# project.net
KiCad netlist of a schematic drawn in EAGLE
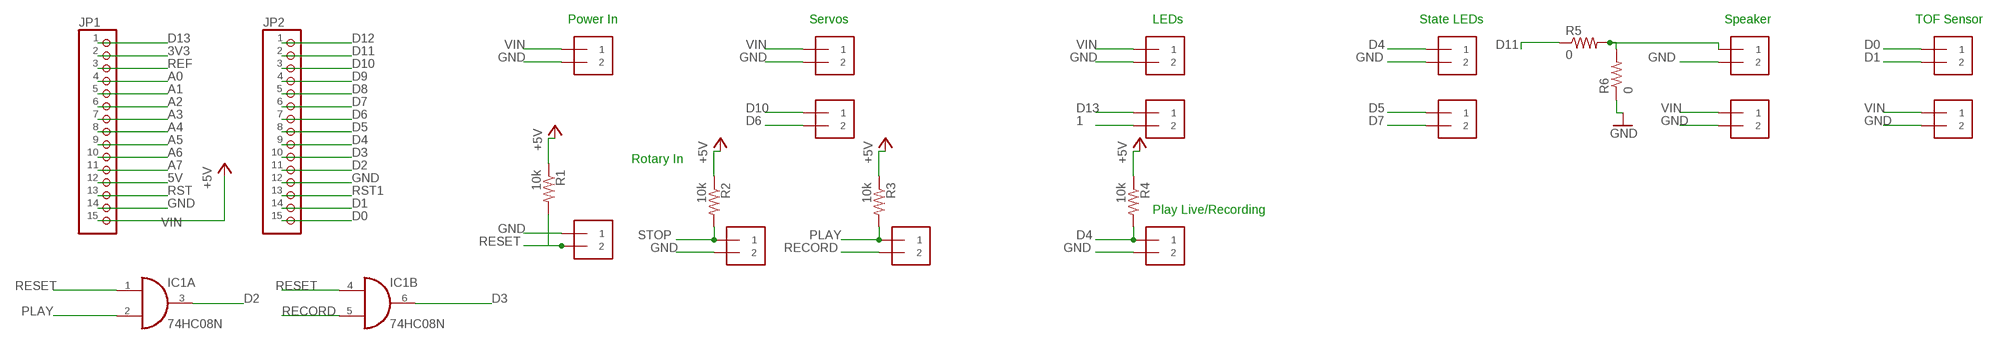
[diagram p0: schematic, sheet 1]

(export (version "E")
  (design (tool "Eeschema 10.0.6"))
  (components
    (comp (ref "IC1")
      (value "74HC08N")
      (footprint "eagle-import:DIL14")
      (libsource (lib "eagle-import") (part "7408NHC"))
    )
    (comp (ref "J1")
      (value "1X2-3.5MM")
      (footprint "eagle-import:1X2-3.5MM")
      (libsource (lib "eagle-import") (part "1X2-3.5MM"))
    )
    (comp (ref "J2")
      (value "1X2-3.5MM")
      (footprint "eagle-import:1X2-3.5MM")
      (libsource (lib "eagle-import") (part "1X2-3.5MM"))
    )
    (comp (ref "J3")
      (value "1X2-3.5MM")
      (footprint "eagle-import:1X2-3.5MM")
      (libsource (lib "eagle-import") (part "1X2-3.5MM"))
    )
    (comp (ref "J4")
      (value "1X2-3.5MM")
      (footprint "eagle-import:1X2-3.5MM")
      (libsource (lib "eagle-import") (part "1X2-3.5MM"))
    )
    (comp (ref "JP1")
      (value "PINHD-1X15")
      (footprint "eagle-import:1X15")
      (libsource (lib "eagle-import") (part "PINHD-1X15"))
    )
    (comp (ref "JP2")
      (value "PINHD-1X15")
      (footprint "eagle-import:1X15")
      (libsource (lib "eagle-import") (part "PINHD-1X15"))
    )
    (comp (ref "LED1")
      (value "1X2-3.5MM")
      (footprint "eagle-import:1X2-3.5MM")
      (libsource (lib "eagle-import") (part "1X2-3.5MM"))
    )
    (comp (ref "LED2_3")
      (value "1X2-3.5MM")
      (footprint "eagle-import:1X2-3.5MM")
      (libsource (lib "eagle-import") (part "1X2-3.5MM"))
    )
    (comp (ref "LED_PWR")
      (value "1X2-3.5MM")
      (footprint "eagle-import:1X2-3.5MM")
      (libsource (lib "eagle-import") (part "1X2-3.5MM"))
    )
    (comp (ref "LED_SIG")
      (value "1X2-3.5MM")
      (footprint "eagle-import:1X2-3.5MM")
      (libsource (lib "eagle-import") (part "1X2-3.5MM"))
    )
    (comp (ref "POWER")
      (value "1X2-3.5MM")
      (footprint "eagle-import:1X2-3.5MM")
      (libsource (lib "eagle-import") (part "1X2-3.5MM"))
    )
    (comp (ref "R1")
      (value "10k")
      (footprint "eagle-import:M0805")
      (libsource (lib "eagle-import") (part "R-US_M0805"))
    )
    (comp (ref "R2")
      (value "10k")
      (footprint "eagle-import:M0805")
      (libsource (lib "eagle-import") (part "R-US_M0805"))
    )
    (comp (ref "R3")
      (value "10k")
      (footprint "eagle-import:M0805")
      (libsource (lib "eagle-import") (part "R-US_M0805"))
    )
    (comp (ref "R4")
      (value "10k")
      (footprint "eagle-import:M0805")
      (libsource (lib "eagle-import") (part "R-US_M0805"))
    )
    (comp (ref "R5")
      (value "0")
      (footprint "eagle-import:M0805")
      (libsource (lib "eagle-import") (part "R-US_M0805"))
    )
    (comp (ref "R6")
      (value "0")
      (footprint "eagle-import:M0805")
      (libsource (lib "eagle-import") (part "R-US_M0805"))
    )
    (comp (ref "SERVO_PWR")
      (value "1X2-3.5MM")
      (footprint "eagle-import:1X2-3.5MM")
      (libsource (lib "eagle-import") (part "1X2-3.5MM"))
    )
    (comp (ref "SERVO_SIG")
      (value "1X2-3.5MM")
      (footprint "eagle-import:1X2-3.5MM")
      (libsource (lib "eagle-import") (part "1X2-3.5MM"))
    )
    (comp (ref "SPK_PWR")
      (value "1X2-3.5MM")
      (footprint "eagle-import:1X2-3.5MM")
      (libsource (lib "eagle-import") (part "1X2-3.5MM"))
    )
    (comp (ref "SPK_SIG")
      (value "1X2-3.5MM")
      (footprint "eagle-import:1X2-3.5MM")
      (libsource (lib "eagle-import") (part "1X2-3.5MM"))
    )
    (comp (ref "TOF_PWR")
      (value "1X2-3.5MM")
      (footprint "eagle-import:1X2-3.5MM")
      (libsource (lib "eagle-import") (part "1X2-3.5MM"))
    )
    (comp (ref "TOF_SIG")
      (value "1X2-3.5MM")
      (footprint "eagle-import:1X2-3.5MM")
      (libsource (lib "eagle-import") (part "1X2-3.5MM"))
    )
  )
  (nets
    (net (code "1") (name "+5V") (class "Default")
      (node (ref "JP1") (pin "15") (pinfunction "15_15") (pintype "passive"))
      (node (ref "LED_PWR") (pin "1") (pinfunction "1_1") (pintype "passive"))
      (node (ref "POWER") (pin "1") (pinfunction "1_1") (pintype "passive"))
      (node (ref "R1") (pin "1") (pinfunction "1_1") (pintype "passive"))
      (node (ref "R2") (pin "1") (pinfunction "1_1") (pintype "passive"))
      (node (ref "R3") (pin "1") (pinfunction "1_1") (pintype "passive"))
      (node (ref "R4") (pin "1") (pinfunction "1_1") (pintype "passive"))
      (node (ref "SERVO_PWR") (pin "1") (pinfunction "1_1") (pintype "passive"))
      (node (ref "SPK_PWR") (pin "1") (pinfunction "1_1") (pintype "passive"))
      (node (ref "TOF_PWR") (pin "1") (pinfunction "1_1") (pintype "passive"))
    )
    (net (code "2") (name "/1") (class "Default")
      (node (ref "LED_SIG") (pin "2") (pinfunction "2_2") (pintype "passive"))
    )
    (net (code "3") (name "/3V3") (class "Default")
      (node (ref "JP1") (pin "2") (pinfunction "2_2") (pintype "passive"))
    )
    (net (code "4") (name "/5V") (class "Default")
      (node (ref "JP1") (pin "12") (pinfunction "12_12") (pintype "passive"))
    )
    (net (code "5") (name "/A0") (class "Default")
      (node (ref "JP1") (pin "4") (pinfunction "4_4") (pintype "passive"))
    )
    (net (code "6") (name "/A1") (class "Default")
      (node (ref "JP1") (pin "5") (pinfunction "5_5") (pintype "passive"))
    )
    (net (code "7") (name "/A2") (class "Default")
      (node (ref "JP1") (pin "6") (pinfunction "6_6") (pintype "passive"))
    )
    (net (code "8") (name "/A3") (class "Default")
      (node (ref "JP1") (pin "7") (pinfunction "7_7") (pintype "passive"))
    )
    (net (code "9") (name "/A4") (class "Default")
      (node (ref "JP1") (pin "8") (pinfunction "8_8") (pintype "passive"))
    )
    (net (code "10") (name "/A5") (class "Default")
      (node (ref "JP1") (pin "9") (pinfunction "9_9") (pintype "passive"))
    )
    (net (code "11") (name "/A6") (class "Default")
      (node (ref "JP1") (pin "10") (pinfunction "10_10") (pintype "passive"))
    )
    (net (code "12") (name "/A7") (class "Default")
      (node (ref "JP1") (pin "11") (pinfunction "11_11") (pintype "passive"))
    )
    (net (code "13") (name "/D0") (class "Default")
      (node (ref "JP2") (pin "15") (pinfunction "15_15") (pintype "passive"))
      (node (ref "TOF_SIG") (pin "1") (pinfunction "1_1") (pintype "passive"))
    )
    (net (code "14") (name "/D1") (class "Default")
      (node (ref "JP2") (pin "14") (pinfunction "14_14") (pintype "passive"))
      (node (ref "TOF_SIG") (pin "2") (pinfunction "2_2") (pintype "passive"))
    )
    (net (code "15") (name "/D2") (class "Default")
      (node (ref "IC1") (pin "3") (pinfunction "O_3") (pintype "output"))
      (node (ref "JP2") (pin "11") (pinfunction "11_11") (pintype "passive"))
    )
    (net (code "16") (name "/D3") (class "Default")
      (node (ref "IC1") (pin "6") (pinfunction "O_6") (pintype "output"))
      (node (ref "JP2") (pin "10") (pinfunction "10_10") (pintype "passive"))
    )
    (net (code "17") (name "/D4") (class "Default")
      (node (ref "J1") (pin "1") (pinfunction "1_1") (pintype "passive"))
      (node (ref "JP2") (pin "9") (pinfunction "9_9") (pintype "passive"))
      (node (ref "LED1") (pin "1") (pinfunction "1_1") (pintype "passive"))
      (node (ref "R4") (pin "2") (pinfunction "2_2") (pintype "passive"))
    )
    (net (code "18") (name "/D5") (class "Default")
      (node (ref "JP2") (pin "8") (pinfunction "8_8") (pintype "passive"))
      (node (ref "LED2_3") (pin "1") (pinfunction "1_1") (pintype "passive"))
    )
    (net (code "19") (name "/D6") (class "Default")
      (node (ref "JP2") (pin "7") (pinfunction "7_7") (pintype "passive"))
      (node (ref "SERVO_SIG") (pin "2") (pinfunction "2_2") (pintype "passive"))
    )
    (net (code "20") (name "/D7") (class "Default")
      (node (ref "JP2") (pin "6") (pinfunction "6_6") (pintype "passive"))
      (node (ref "LED2_3") (pin "2") (pinfunction "2_2") (pintype "passive"))
    )
    (net (code "21") (name "/D8") (class "Default")
      (node (ref "JP2") (pin "5") (pinfunction "5_5") (pintype "passive"))
    )
    (net (code "22") (name "/D9") (class "Default")
      (node (ref "JP2") (pin "4") (pinfunction "4_4") (pintype "passive"))
    )
    (net (code "23") (name "/D10") (class "Default")
      (node (ref "JP2") (pin "3") (pinfunction "3_3") (pintype "passive"))
      (node (ref "SERVO_SIG") (pin "1") (pinfunction "1_1") (pintype "passive"))
    )
    (net (code "24") (name "/D11") (class "Default")
      (node (ref "JP2") (pin "2") (pinfunction "2_2") (pintype "passive"))
      (node (ref "R5") (pin "1") (pinfunction "1_1") (pintype "passive"))
    )
    (net (code "25") (name "/D12") (class "Default")
      (node (ref "JP2") (pin "1") (pinfunction "1_1") (pintype "passive"))
    )
    (net (code "26") (name "/D13") (class "Default")
      (node (ref "JP1") (pin "1") (pinfunction "1_1") (pintype "passive"))
      (node (ref "LED_SIG") (pin "1") (pinfunction "1_1") (pintype "passive"))
    )
    (net (code "27") (name "/PLAY") (class "Default")
      (node (ref "IC1") (pin "2") (pinfunction "I1_2") (pintype "input"))
      (node (ref "J2") (pin "1") (pinfunction "1_1") (pintype "passive"))
      (node (ref "R3") (pin "2") (pinfunction "2_2") (pintype "passive"))
    )
    (net (code "28") (name "/RECORD") (class "Default")
      (node (ref "IC1") (pin "5") (pinfunction "I1_5") (pintype "input"))
      (node (ref "J2") (pin "2") (pinfunction "2_2") (pintype "passive"))
    )
    (net (code "29") (name "/REF") (class "Default")
      (node (ref "JP1") (pin "3") (pinfunction "3_3") (pintype "passive"))
    )
    (net (code "30") (name "/RESET") (class "Default")
      (node (ref "IC1") (pin "1") (pinfunction "I0_1") (pintype "input"))
      (node (ref "IC1") (pin "4") (pinfunction "I0_4") (pintype "input"))
      (node (ref "J4") (pin "2") (pinfunction "2_2") (pintype "passive"))
      (node (ref "R1") (pin "2") (pinfunction "2_2") (pintype "passive"))
    )
    (net (code "31") (name "/RST") (class "Default")
      (node (ref "JP1") (pin "13") (pinfunction "13_13") (pintype "passive"))
    )
    (net (code "32") (name "/RST1") (class "Default")
      (node (ref "JP2") (pin "13") (pinfunction "13_13") (pintype "passive"))
    )
    (net (code "33") (name "/STOP") (class "Default")
      (node (ref "J3") (pin "1") (pinfunction "1_1") (pintype "passive"))
      (node (ref "R2") (pin "2") (pinfunction "2_2") (pintype "passive"))
    )
    (net (code "34") (name "GND") (class "Default")
      (node (ref "J1") (pin "2") (pinfunction "2_2") (pintype "passive"))
      (node (ref "J3") (pin "2") (pinfunction "2_2") (pintype "passive"))
      (node (ref "J4") (pin "1") (pinfunction "1_1") (pintype "passive"))
      (node (ref "JP1") (pin "14") (pinfunction "14_14") (pintype "passive"))
      (node (ref "JP2") (pin "12") (pinfunction "12_12") (pintype "passive"))
      (node (ref "LED1") (pin "2") (pinfunction "2_2") (pintype "passive"))
      (node (ref "LED_PWR") (pin "2") (pinfunction "2_2") (pintype "passive"))
      (node (ref "POWER") (pin "2") (pinfunction "2_2") (pintype "passive"))
      (node (ref "R6") (pin "1") (pinfunction "1_1") (pintype "passive"))
      (node (ref "SERVO_PWR") (pin "2") (pinfunction "2_2") (pintype "passive"))
      (node (ref "SPK_PWR") (pin "2") (pinfunction "2_2") (pintype "passive"))
      (node (ref "SPK_SIG") (pin "2") (pinfunction "2_2") (pintype "passive"))
      (node (ref "TOF_PWR") (pin "2") (pinfunction "2_2") (pintype "passive"))
    )
    (net (code "35") (name "Net-(R5-Pad2)") (class "Default")
      (node (ref "R5") (pin "2") (pinfunction "2_2") (pintype "passive"))
      (node (ref "R6") (pin "2") (pinfunction "2_2") (pintype "passive"))
      (node (ref "SPK_SIG") (pin "1") (pinfunction "1_1") (pintype "passive"))
    )
  )
)
